# LiPo_Charger_UPDI_Adapter.net
KiCad netlist of a schematic drawn in EAGLE
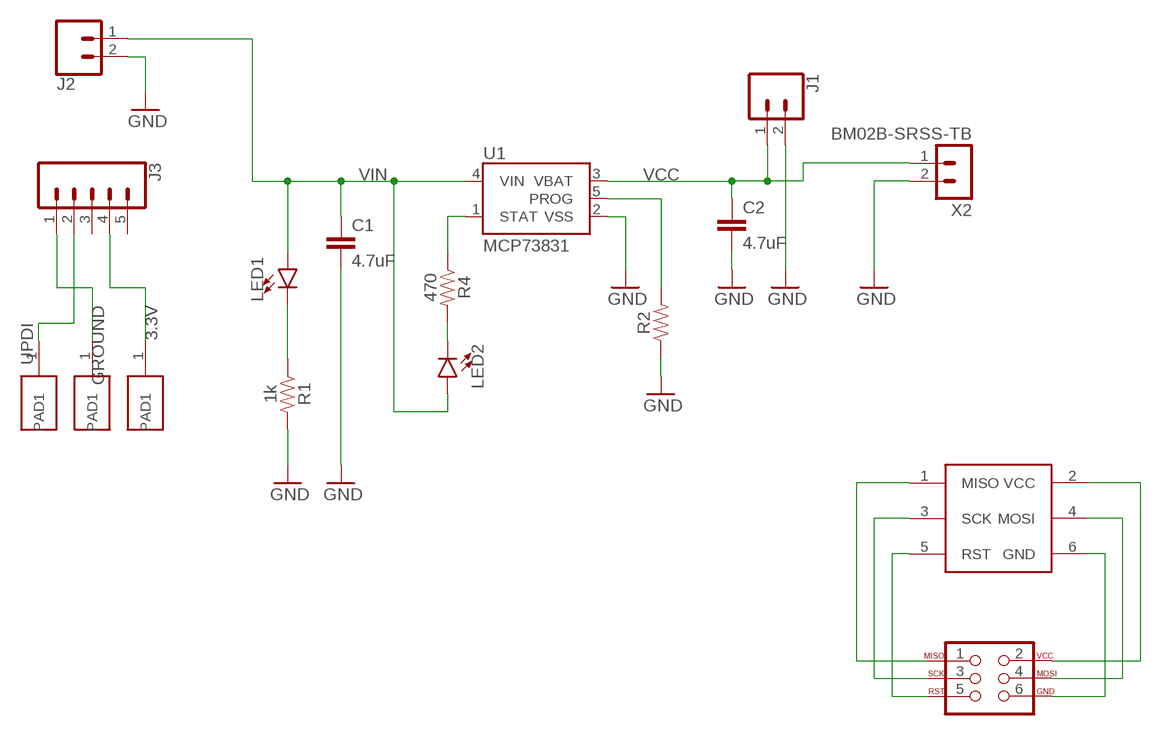
[diagram p0: schematic, sheet 1]

(export (version "E")
  (design (tool "Eeschema 10.0.6"))
  (components
    (comp (ref "C1")
      (value "4.7uF")
      (footprint "eagle-import:1206")
      (libsource (lib "eagle-import") (part "4.7UF-1206-16V-(+80/-20%)"))
    )
    (comp (ref "C2")
      (value "4.7uF")
      (footprint "eagle-import:1206")
      (libsource (lib "eagle-import") (part "4.7UF-1206-16V-(+80/-20%)"))
    )
    (comp (ref "J1")
      (value "CONN_02")
      (footprint "eagle-import:1X02")
      (libsource (lib "eagle-import") (part "CONN_02"))
    )
    (comp (ref "J2")
      (value "CONN_02")
      (footprint "eagle-import:1X02")
      (libsource (lib "eagle-import") (part "SparkFun-Connectors_CONN_02"))
    )
    (comp (ref "J3")
      (value "CONN_05")
      (footprint "eagle-import:1X05")
      (libsource (lib "eagle-import") (part "CONN_05"))
    )
    (comp (ref "J4")
      (value "AVR_SPI_PROG_3X2NS")
      (footprint "eagle-import:2X3-NS")
      (libsource (lib "eagle-import") (part "AVR_SPI_PROG_3X2NS"))
    )
    (comp (ref "LED1")
      (value "LED-FKIT-1206")
      (footprint "eagle-import:FKIT-LED-1206")
      (libsource (lib "eagle-import") (part "LED-FKIT-1206"))
    )
    (comp (ref "LED2")
      (value "LED-FKIT-1206")
      (footprint "eagle-import:FKIT-LED-1206")
      (libsource (lib "eagle-import") (part "LED-FKIT-1206"))
    )
    (comp (ref "R1")
      (value "1k")
      (footprint "eagle-import:1206")
      (libsource (lib "eagle-import") (part "RESISTOR1206"))
    )
    (comp (ref "R2")
      (value "RESISTORAXIAL-0.3")
      (footprint "eagle-import:AXIAL-0.3")
      (libsource (lib "eagle-import") (part "RESISTORAXIAL-0.3"))
    )
    (comp (ref "R4")
      (value "470")
      (footprint "eagle-import:1206")
      (libsource (lib "eagle-import") (part "RESISTOR1206"))
    )
    (comp (ref "U$1")
      (value "SINGLE_1.27MM_HOLE")
      (footprint "eagle-import:1.27MM_SINGLE_HOLE")
      (libsource (lib "eagle-import") (part "SINGLE_1.27MM_HOLE"))
    )
    (comp (ref "U$2")
      (value "SINGLE_1.27MM_HOLE")
      (footprint "eagle-import:1.27MM_SINGLE_HOLE")
      (libsource (lib "eagle-import") (part "SINGLE_1.27MM_HOLE"))
    )
    (comp (ref "U$3")
      (value "SINGLE_1.27MM_HOLE")
      (footprint "eagle-import:1.27MM_SINGLE_HOLE")
      (libsource (lib "eagle-import") (part "SINGLE_1.27MM_HOLE"))
    )
    (comp (ref "U$4")
      (value "2X3_1.27MM_ICSP")
      (footprint "eagle-import:2X3_1.27MM_ICSP")
      (libsource (lib "eagle-import") (part "2X3_1.27MM_ICSP"))
    )
    (comp (ref "U1")
      (value "MCP73831")
      (footprint "eagle-import:SOT23-5")
      (libsource (lib "eagle-import") (part "MCP73831"))
    )
    (comp (ref "X2")
      (value "BM02B-SRSS-TB")
      (footprint "eagle-import:BM02B-SRSS-TB")
      (libsource (lib "eagle-import") (part "BM02B-SRSS-TB"))
    )
  )
  (nets
    (net (code "1") (name "/3.3V") (class "Default")
      (node (ref "J3") (pin "4") (pinfunction "4_4") (pintype "passive"))
      (node (ref "U$3") (pin "1") (pinfunction "PAD1_1") (pintype "bidirectional"))
    )
    (net (code "2") (name "/GROUND") (class "Default")
      (node (ref "J3") (pin "1") (pinfunction "1_1") (pintype "passive"))
      (node (ref "U$2") (pin "1") (pinfunction "PAD1_1") (pintype "bidirectional"))
    )
    (net (code "3") (name "/UPDI") (class "Default")
      (node (ref "J3") (pin "2") (pinfunction "2_2") (pintype "passive"))
      (node (ref "U$1") (pin "1") (pinfunction "PAD1_1") (pintype "bidirectional"))
    )
    (net (code "4") (name "/VCC") (class "Default")
      (node (ref "C2") (pin "1") (pinfunction "1_1") (pintype "passive"))
      (node (ref "J1") (pin "1") (pinfunction "1_1") (pintype "passive"))
      (node (ref "U1") (pin "3") (pinfunction "VBAT_3") (pintype "power_in"))
      (node (ref "X2") (pin "1") (pinfunction "1_1") (pintype "passive"))
    )
    (net (code "5") (name "/VIN") (class "Default")
      (node (ref "C1") (pin "1") (pinfunction "1_1") (pintype "passive"))
      (node (ref "J2") (pin "1") (pinfunction "1_1") (pintype "passive"))
      (node (ref "LED1") (pin "A") (pinfunction "A_A") (pintype "passive"))
      (node (ref "LED2") (pin "A") (pinfunction "A_A") (pintype "passive"))
      (node (ref "U1") (pin "4") (pinfunction "VIN_4") (pintype "power_in"))
    )
    (net (code "6") (name "GND") (class "Default")
      (node (ref "C1") (pin "2") (pinfunction "2_2") (pintype "passive"))
      (node (ref "C2") (pin "2") (pinfunction "2_2") (pintype "passive"))
      (node (ref "J1") (pin "2") (pinfunction "2_2") (pintype "passive"))
      (node (ref "J2") (pin "2") (pinfunction "2_2") (pintype "passive"))
      (node (ref "R1") (pin "2") (pinfunction "2_2") (pintype "passive"))
      (node (ref "R2") (pin "P$1") (pinfunction "1_P$1") (pintype "passive"))
      (node (ref "U1") (pin "2") (pinfunction "VSS_2") (pintype "power_in"))
      (node (ref "X2") (pin "2") (pinfunction "2_2") (pintype "passive"))
    )
    (net (code "7") (name "Net-(LED1-PadC)") (class "Default")
      (node (ref "LED1") (pin "C") (pinfunction "C_C") (pintype "passive"))
      (node (ref "R1") (pin "1") (pinfunction "1_1") (pintype "passive"))
    )
    (net (code "8") (name "Net-(LED2-PadC)") (class "Default")
      (node (ref "LED2") (pin "C") (pinfunction "C_C") (pintype "passive"))
      (node (ref "R4") (pin "2") (pinfunction "2_2") (pintype "passive"))
    )
    (net (code "9") (name "Net-(R2-2)") (class "Default")
      (node (ref "R2") (pin "P$2") (pinfunction "2_P$2") (pintype "passive"))
      (node (ref "U1") (pin "5") (pinfunction "PROG_5") (pintype "input"))
    )
    (net (code "10") (name "Net-(U$4-GND)") (class "Default")
      (node (ref "J4") (pin "6") (pinfunction "6_6") (pintype "passive"))
      (node (ref "U$4") (pin "6") (pinfunction "GND_6") (pintype "bidirectional"))
    )
    (net (code "11") (name "Net-(U$4-MISO)") (class "Default")
      (node (ref "J4") (pin "1") (pinfunction "1_1") (pintype "passive"))
      (node (ref "U$4") (pin "1") (pinfunction "MISO_1") (pintype "bidirectional"))
    )
    (net (code "12") (name "Net-(U$4-MOSI)") (class "Default")
      (node (ref "J4") (pin "4") (pinfunction "4_4") (pintype "passive"))
      (node (ref "U$4") (pin "4") (pinfunction "MOSI_4") (pintype "bidirectional"))
    )
    (net (code "13") (name "Net-(U$4-RST)") (class "Default")
      (node (ref "J4") (pin "5") (pinfunction "5_5") (pintype "passive"))
      (node (ref "U$4") (pin "5") (pinfunction "RST_5") (pintype "bidirectional"))
    )
    (net (code "14") (name "Net-(U$4-SCK)") (class "Default")
      (node (ref "J4") (pin "3") (pinfunction "3_3") (pintype "passive"))
      (node (ref "U$4") (pin "3") (pinfunction "SCK_3") (pintype "bidirectional"))
    )
    (net (code "15") (name "Net-(U$4-VCC)") (class "Default")
      (node (ref "J4") (pin "2") (pinfunction "2_2") (pintype "passive"))
      (node (ref "U$4") (pin "2") (pinfunction "VCC_2") (pintype "bidirectional"))
    )
    (net (code "16") (name "Net-(U1-STAT)") (class "Default")
      (node (ref "R4") (pin "1") (pinfunction "1_1") (pintype "passive"))
      (node (ref "U1") (pin "1") (pinfunction "STAT_1") (pintype "output"))
    )
    (net (code "17") (name "unconnected-(J3-Pad3)") (class "Default")
      (node (ref "J3") (pin "3") (pinfunction "3_3") (pintype "passive"))
    )
    (net (code "18") (name "unconnected-(J3-Pad5)") (class "Default")
      (node (ref "J3") (pin "5") (pinfunction "5_5") (pintype "passive"))
    )
  )
)
